# S7CAS-PLEIADES-CARTE-MERE_P07_FPGA_MISC.net
KiCad netlist of a schematic drawn in Altium Designer
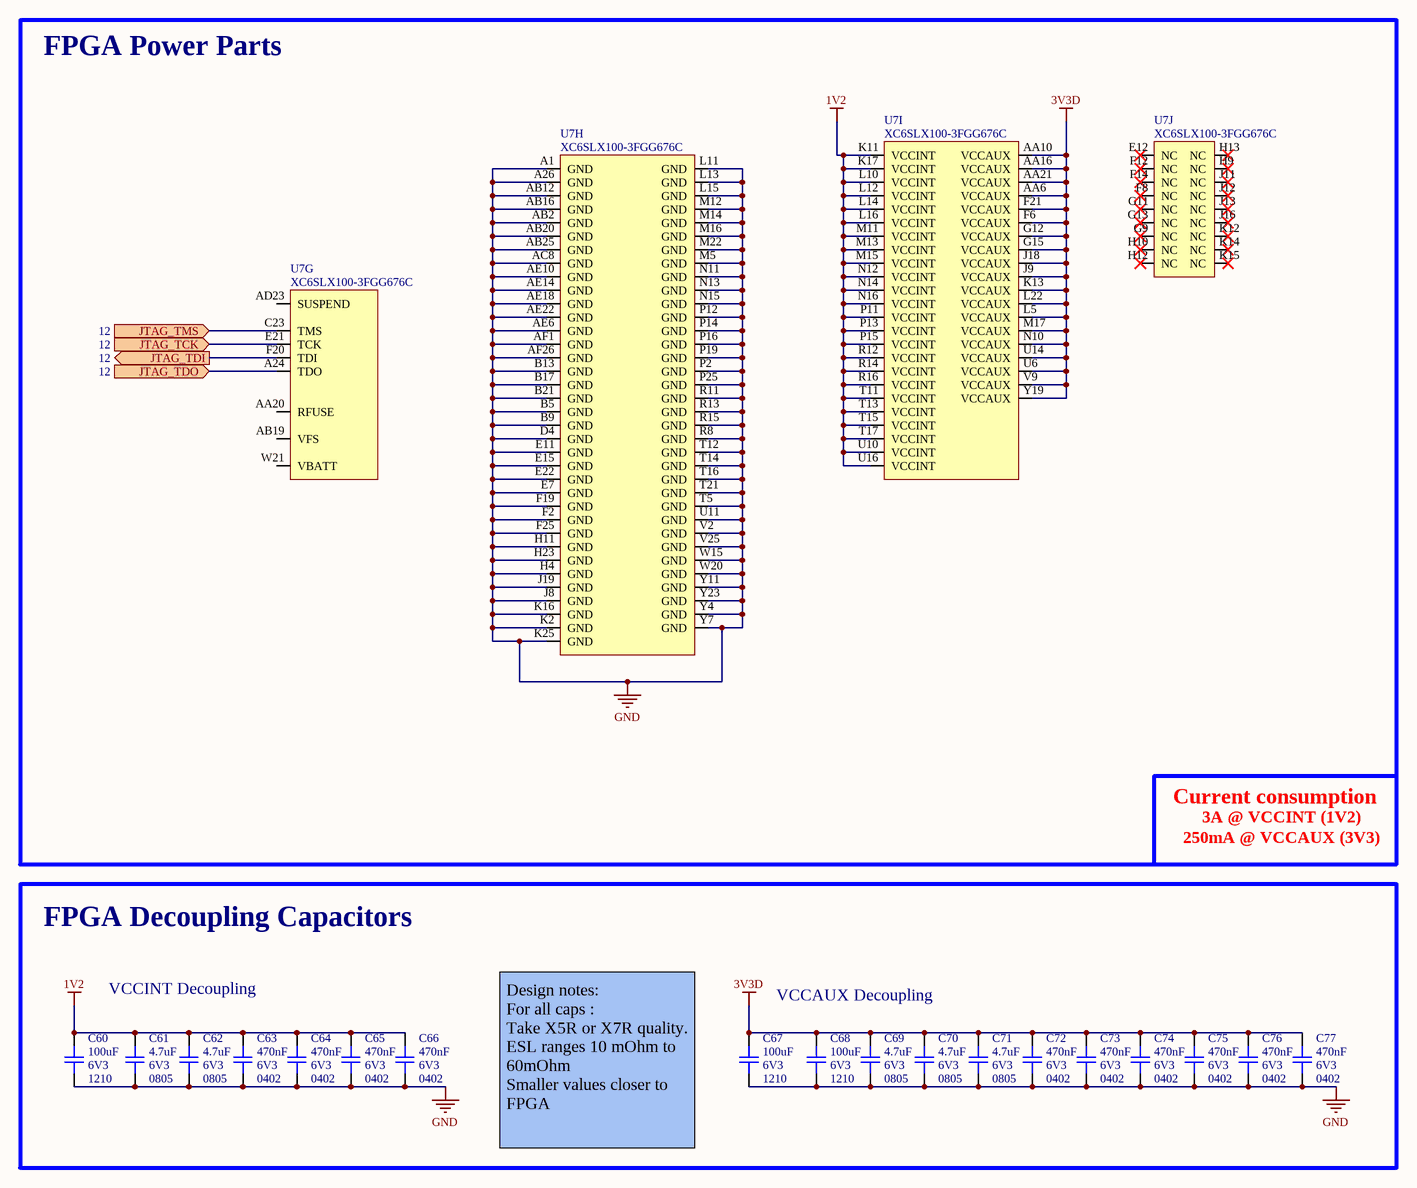
[diagram p0: S7CAS-PLEIADES-CARTE-MERE_P07_FPGA_MISC.SchDoc]

(export (version "E")
  (design (tool "Eeschema 10.0.6"))
  (components
    (comp (ref "C60")
      (value "100uF")
      (footprint "CAP_1210")
      (description "CAP - 1210")
      (fields
        (field (name "VOLTAGE") "6V3")
        (field (name "PACKAGE") "1210")
        (field (name "CREATEDBY") "Jonathan Bouchard")
      )
      (libsource (lib "S7CAS_LIB2021") (part "CAP - 1210"))
    )
    (comp (ref "C61")
      (value "4.7uF")
      (footprint "CAP_0805")
      (description "CAP - 0805")
      (fields
        (field (name "VOLTAGE") "6V3")
        (field (name "PACKAGE") "0805")
        (field (name "CREATEDBY") "Jonathan Bouchard")
      )
      (libsource (lib "S7CAS_LIB2021") (part "CAP - 0805"))
    )
    (comp (ref "C62")
      (value "4.7uF")
      (footprint "CAP_0805")
      (description "CAP - 0805")
      (fields
        (field (name "VOLTAGE") "6V3")
        (field (name "PACKAGE") "0805")
        (field (name "CREATEDBY") "Jonathan Bouchard")
      )
      (libsource (lib "S7CAS_LIB2021") (part "CAP - 0805"))
    )
    (comp (ref "C63")
      (value "470nF")
      (footprint "CAP_0402")
      (description "CAP - 0402")
      (fields
        (field (name "VOLTAGE") "6V3")
        (field (name "PACKAGE") "0402")
        (field (name "CREATEDBY") "Jonathan Bouchard")
      )
      (libsource (lib "S7CAS_LIB2021") (part "CAP - 0402"))
    )
    (comp (ref "C64")
      (value "470nF")
      (footprint "CAP_0402")
      (description "CAP - 0402")
      (fields
        (field (name "VOLTAGE") "6V3")
        (field (name "PACKAGE") "0402")
        (field (name "CREATEDBY") "Jonathan Bouchard")
      )
      (libsource (lib "S7CAS_LIB2021") (part "CAP - 0402"))
    )
    (comp (ref "C65")
      (value "470nF")
      (footprint "CAP_0402")
      (description "CAP - 0402")
      (fields
        (field (name "VOLTAGE") "6V3")
        (field (name "PACKAGE") "0402")
        (field (name "CREATEDBY") "Jonathan Bouchard")
      )
      (libsource (lib "S7CAS_LIB2021") (part "CAP - 0402"))
    )
    (comp (ref "C66")
      (value "470nF")
      (footprint "CAP_0402")
      (description "CAP - 0402")
      (fields
        (field (name "VOLTAGE") "6V3")
        (field (name "PACKAGE") "0402")
        (field (name "CREATEDBY") "Jonathan Bouchard")
      )
      (libsource (lib "S7CAS_LIB2021") (part "CAP - 0402"))
    )
    (comp (ref "C67")
      (value "100uF")
      (footprint "CAP_1210")
      (description "CAP - 1210")
      (fields
        (field (name "VOLTAGE") "6V3")
        (field (name "PACKAGE") "1210")
        (field (name "CREATEDBY") "Jonathan Bouchard")
      )
      (libsource (lib "S7CAS_LIB2021") (part "CAP - 1210"))
    )
    (comp (ref "C68")
      (value "100uF")
      (footprint "CAP_1210")
      (description "CAP - 1210")
      (fields
        (field (name "VOLTAGE") "6V3")
        (field (name "PACKAGE") "1210")
        (field (name "CREATEDBY") "Jonathan Bouchard")
      )
      (libsource (lib "S7CAS_LIB2021") (part "CAP - 1210"))
    )
    (comp (ref "C69")
      (value "4.7uF")
      (footprint "CAP_0805")
      (description "CAP - 0805")
      (fields
        (field (name "VOLTAGE") "6V3")
        (field (name "PACKAGE") "0805")
        (field (name "CREATEDBY") "Jonathan Bouchard")
      )
      (libsource (lib "S7CAS_LIB2021") (part "CAP - 0805"))
    )
    (comp (ref "C70")
      (value "4.7uF")
      (footprint "CAP_0805")
      (description "CAP - 0805")
      (fields
        (field (name "VOLTAGE") "6V3")
        (field (name "PACKAGE") "0805")
        (field (name "CREATEDBY") "Jonathan Bouchard")
      )
      (libsource (lib "S7CAS_LIB2021") (part "CAP - 0805"))
    )
    (comp (ref "C71")
      (value "4.7uF")
      (footprint "CAP_0805")
      (description "CAP - 0805")
      (fields
        (field (name "VOLTAGE") "6V3")
        (field (name "PACKAGE") "0805")
        (field (name "CREATEDBY") "Jonathan Bouchard")
      )
      (libsource (lib "S7CAS_LIB2021") (part "CAP - 0805"))
    )
    (comp (ref "C72")
      (value "470nF")
      (footprint "CAP_0402")
      (description "CAP - 0402")
      (fields
        (field (name "VOLTAGE") "6V3")
        (field (name "PACKAGE") "0402")
        (field (name "CREATEDBY") "Jonathan Bouchard")
      )
      (libsource (lib "S7CAS_LIB2021") (part "CAP - 0402"))
    )
    (comp (ref "C73")
      (value "470nF")
      (footprint "CAP_0402")
      (description "CAP - 0402")
      (fields
        (field (name "VOLTAGE") "6V3")
        (field (name "PACKAGE") "0402")
        (field (name "CREATEDBY") "Jonathan Bouchard")
      )
      (libsource (lib "S7CAS_LIB2021") (part "CAP - 0402"))
    )
    (comp (ref "C74")
      (value "470nF")
      (footprint "CAP_0402")
      (description "CAP - 0402")
      (fields
        (field (name "VOLTAGE") "6V3")
        (field (name "PACKAGE") "0402")
        (field (name "CREATEDBY") "Jonathan Bouchard")
      )
      (libsource (lib "S7CAS_LIB2021") (part "CAP - 0402"))
    )
    (comp (ref "C75")
      (value "470nF")
      (footprint "CAP_0402")
      (description "CAP - 0402")
      (fields
        (field (name "VOLTAGE") "6V3")
        (field (name "PACKAGE") "0402")
        (field (name "CREATEDBY") "Jonathan Bouchard")
      )
      (libsource (lib "S7CAS_LIB2021") (part "CAP - 0402"))
    )
    (comp (ref "C76")
      (value "470nF")
      (footprint "CAP_0402")
      (description "CAP - 0402")
      (fields
        (field (name "VOLTAGE") "6V3")
        (field (name "PACKAGE") "0402")
        (field (name "CREATEDBY") "Jonathan Bouchard")
      )
      (libsource (lib "S7CAS_LIB2021") (part "CAP - 0402"))
    )
    (comp (ref "C77")
      (value "470nF")
      (footprint "CAP_0402")
      (description "CAP - 0402")
      (fields
        (field (name "VOLTAGE") "6V3")
        (field (name "PACKAGE") "0402")
        (field (name "CREATEDBY") "Jonathan Bouchard")
      )
      (libsource (lib "S7CAS_LIB2021") (part "CAP - 0402"))
    )
    (comp (ref "U7")
      (value "XC6SLX100-3FGG676C")
      (footprint "FPGA_XILINX_FGG676")
      (description "FPGA - XILINX SPARTAN 6 480 I/O - BGA-676")
      (fields
        (field (name "VOLTAGE") "1.14 V ~ 1.26 V")
        (field (name "MFG") "Xilinx")
        (field (name "CREATEDBY") "Jonathan Bouchard")
      )
      (libsource (lib "S7CAS_LIB2021") (part "FPGA_XC6SLX100-3FGG676C"))
    )
  )
  (nets
    (net (code "1") (name "/JTAG_TCK") (class "Default")
      (node (ref "U7") (pin "E21") (pinfunction "TCK_E21") (pintype "passive"))
    )
    (net (code "2") (name "/JTAG_TDI") (class "Default")
      (node (ref "U7") (pin "F20") (pinfunction "TDI_F20") (pintype "passive"))
    )
    (net (code "3") (name "/JTAG_TDO") (class "Default")
      (node (ref "U7") (pin "A24") (pinfunction "TDO_A24") (pintype "passive"))
    )
    (net (code "4") (name "/JTAG_TMS") (class "Default")
      (node (ref "U7") (pin "C23") (pinfunction "TMS_C23") (pintype "passive"))
    )
    (net (code "5") (name "1V2") (class "Default")
      (node (ref "C60") (pin "2") (pinfunction "2_2") (pintype "passive"))
      (node (ref "C61") (pin "2") (pinfunction "2_2") (pintype "passive"))
      (node (ref "C62") (pin "2") (pinfunction "2_2") (pintype "passive"))
      (node (ref "C63") (pin "2") (pinfunction "2_2") (pintype "passive"))
      (node (ref "C64") (pin "2") (pinfunction "2_2") (pintype "passive"))
      (node (ref "C65") (pin "2") (pinfunction "2_2") (pintype "passive"))
      (node (ref "C66") (pin "2") (pinfunction "2_2") (pintype "passive"))
      (node (ref "U7") (pin "K11") (pinfunction "VCCINT_K11") (pintype "passive"))
      (node (ref "U7") (pin "K17") (pinfunction "VCCINT_K17") (pintype "passive"))
      (node (ref "U7") (pin "L10") (pinfunction "VCCINT_L10") (pintype "passive"))
      (node (ref "U7") (pin "L12") (pinfunction "VCCINT_L12") (pintype "passive"))
      (node (ref "U7") (pin "L14") (pinfunction "VCCINT_L14") (pintype "passive"))
      (node (ref "U7") (pin "L16") (pinfunction "VCCINT_L16") (pintype "passive"))
      (node (ref "U7") (pin "M11") (pinfunction "VCCINT_M11") (pintype "passive"))
      (node (ref "U7") (pin "M13") (pinfunction "VCCINT_M13") (pintype "passive"))
      (node (ref "U7") (pin "M15") (pinfunction "VCCINT_M15") (pintype "passive"))
      (node (ref "U7") (pin "N12") (pinfunction "VCCINT_N12") (pintype "passive"))
      (node (ref "U7") (pin "N14") (pinfunction "VCCINT_N14") (pintype "passive"))
      (node (ref "U7") (pin "N16") (pinfunction "VCCINT_N16") (pintype "passive"))
      (node (ref "U7") (pin "P11") (pinfunction "VCCINT_P11") (pintype "passive"))
      (node (ref "U7") (pin "P13") (pinfunction "VCCINT_P13") (pintype "passive"))
      (node (ref "U7") (pin "P15") (pinfunction "VCCINT_P15") (pintype "passive"))
      (node (ref "U7") (pin "R12") (pinfunction "VCCINT_R12") (pintype "passive"))
      (node (ref "U7") (pin "R14") (pinfunction "VCCINT_R14") (pintype "passive"))
      (node (ref "U7") (pin "R16") (pinfunction "VCCINT_R16") (pintype "passive"))
      (node (ref "U7") (pin "T11") (pinfunction "VCCINT_T11") (pintype "passive"))
      (node (ref "U7") (pin "T13") (pinfunction "VCCINT_T13") (pintype "passive"))
      (node (ref "U7") (pin "T15") (pinfunction "VCCINT_T15") (pintype "passive"))
      (node (ref "U7") (pin "T17") (pinfunction "VCCINT_T17") (pintype "passive"))
      (node (ref "U7") (pin "U10") (pinfunction "VCCINT_U10") (pintype "passive"))
      (node (ref "U7") (pin "U16") (pinfunction "VCCINT_U16") (pintype "passive"))
    )
    (net (code "6") (name "3V3D") (class "Default")
      (node (ref "C67") (pin "2") (pinfunction "2_2") (pintype "passive"))
      (node (ref "C68") (pin "2") (pinfunction "2_2") (pintype "passive"))
      (node (ref "C69") (pin "2") (pinfunction "2_2") (pintype "passive"))
      (node (ref "C70") (pin "2") (pinfunction "2_2") (pintype "passive"))
      (node (ref "C71") (pin "2") (pinfunction "2_2") (pintype "passive"))
      (node (ref "C72") (pin "2") (pinfunction "2_2") (pintype "passive"))
      (node (ref "C73") (pin "2") (pinfunction "2_2") (pintype "passive"))
      (node (ref "C74") (pin "2") (pinfunction "2_2") (pintype "passive"))
      (node (ref "C75") (pin "2") (pinfunction "2_2") (pintype "passive"))
      (node (ref "C76") (pin "2") (pinfunction "2_2") (pintype "passive"))
      (node (ref "C77") (pin "2") (pinfunction "2_2") (pintype "passive"))
      (node (ref "U7") (pin "AA10") (pinfunction "VCCAUX_AA10") (pintype "passive"))
      (node (ref "U7") (pin "AA16") (pinfunction "VCCAUX_AA16") (pintype "passive"))
      (node (ref "U7") (pin "AA21") (pinfunction "VCCAUX_AA21") (pintype "passive"))
      (node (ref "U7") (pin "AA6") (pinfunction "VCCAUX_AA6") (pintype "passive"))
      (node (ref "U7") (pin "F21") (pinfunction "VCCAUX_F21") (pintype "passive"))
      (node (ref "U7") (pin "F6") (pinfunction "VCCAUX_F6") (pintype "passive"))
      (node (ref "U7") (pin "G12") (pinfunction "VCCAUX_G12") (pintype "passive"))
      (node (ref "U7") (pin "G15") (pinfunction "VCCAUX_G15") (pintype "passive"))
      (node (ref "U7") (pin "J18") (pinfunction "VCCAUX_J18") (pintype "passive"))
      (node (ref "U7") (pin "J9") (pinfunction "VCCAUX_J9") (pintype "passive"))
      (node (ref "U7") (pin "K13") (pinfunction "VCCAUX_K13") (pintype "passive"))
      (node (ref "U7") (pin "L22") (pinfunction "VCCAUX_L22") (pintype "passive"))
      (node (ref "U7") (pin "L5") (pinfunction "VCCAUX_L5") (pintype "passive"))
      (node (ref "U7") (pin "M17") (pinfunction "VCCAUX_M17") (pintype "passive"))
      (node (ref "U7") (pin "N10") (pinfunction "VCCAUX_N10") (pintype "passive"))
      (node (ref "U7") (pin "U14") (pinfunction "VCCAUX_U14") (pintype "passive"))
      (node (ref "U7") (pin "U6") (pinfunction "VCCAUX_U6") (pintype "passive"))
      (node (ref "U7") (pin "V9") (pinfunction "VCCAUX_V9") (pintype "passive"))
      (node (ref "U7") (pin "Y19") (pinfunction "VCCAUX_Y19") (pintype "passive"))
    )
    (net (code "7") (name "GND") (class "Default")
      (node (ref "C60") (pin "1") (pinfunction "1_1") (pintype "passive"))
      (node (ref "C61") (pin "1") (pinfunction "1_1") (pintype "passive"))
      (node (ref "C62") (pin "1") (pinfunction "1_1") (pintype "passive"))
      (node (ref "C63") (pin "1") (pinfunction "1_1") (pintype "passive"))
      (node (ref "C64") (pin "1") (pinfunction "1_1") (pintype "passive"))
      (node (ref "C65") (pin "1") (pinfunction "1_1") (pintype "passive"))
      (node (ref "C66") (pin "1") (pinfunction "1_1") (pintype "passive"))
      (node (ref "C67") (pin "1") (pinfunction "1_1") (pintype "passive"))
      (node (ref "C68") (pin "1") (pinfunction "1_1") (pintype "passive"))
      (node (ref "C69") (pin "1") (pinfunction "1_1") (pintype "passive"))
      (node (ref "C70") (pin "1") (pinfunction "1_1") (pintype "passive"))
      (node (ref "C71") (pin "1") (pinfunction "1_1") (pintype "passive"))
      (node (ref "C72") (pin "1") (pinfunction "1_1") (pintype "passive"))
      (node (ref "C73") (pin "1") (pinfunction "1_1") (pintype "passive"))
      (node (ref "C74") (pin "1") (pinfunction "1_1") (pintype "passive"))
      (node (ref "C75") (pin "1") (pinfunction "1_1") (pintype "passive"))
      (node (ref "C76") (pin "1") (pinfunction "1_1") (pintype "passive"))
      (node (ref "C77") (pin "1") (pinfunction "1_1") (pintype "passive"))
      (node (ref "U7") (pin "A1") (pinfunction "GND_A1") (pintype "passive"))
      (node (ref "U7") (pin "A26") (pinfunction "GND_A26") (pintype "passive"))
      (node (ref "U7") (pin "AB12") (pinfunction "GND_AB12") (pintype "passive"))
      (node (ref "U7") (pin "AB16") (pinfunction "GND_AB16") (pintype "passive"))
      (node (ref "U7") (pin "AB2") (pinfunction "GND_AB2") (pintype "passive"))
      (node (ref "U7") (pin "AB20") (pinfunction "GND_AB20") (pintype "passive"))
      (node (ref "U7") (pin "AB25") (pinfunction "GND_AB25") (pintype "passive"))
      (node (ref "U7") (pin "AC8") (pinfunction "GND_AC8") (pintype "passive"))
      (node (ref "U7") (pin "AE10") (pinfunction "GND_AE10") (pintype "passive"))
      (node (ref "U7") (pin "AE14") (pinfunction "GND_AE14") (pintype "passive"))
      (node (ref "U7") (pin "AE18") (pinfunction "GND_AE18") (pintype "passive"))
      (node (ref "U7") (pin "AE22") (pinfunction "GND_AE22") (pintype "passive"))
      (node (ref "U7") (pin "AE6") (pinfunction "GND_AE6") (pintype "passive"))
      (node (ref "U7") (pin "AF1") (pinfunction "GND_AF1") (pintype "passive"))
      (node (ref "U7") (pin "AF26") (pinfunction "GND_AF26") (pintype "passive"))
      (node (ref "U7") (pin "B13") (pinfunction "GND_B13") (pintype "passive"))
      (node (ref "U7") (pin "B17") (pinfunction "GND_B17") (pintype "passive"))
      (node (ref "U7") (pin "B21") (pinfunction "GND_B21") (pintype "passive"))
      (node (ref "U7") (pin "B5") (pinfunction "GND_B5") (pintype "passive"))
      (node (ref "U7") (pin "B9") (pinfunction "GND_B9") (pintype "passive"))
      (node (ref "U7") (pin "D4") (pinfunction "GND_D4") (pintype "passive"))
      (node (ref "U7") (pin "E11") (pinfunction "GND_E11") (pintype "passive"))
      (node (ref "U7") (pin "E15") (pinfunction "GND_E15") (pintype "passive"))
      (node (ref "U7") (pin "E22") (pinfunction "GND_E22") (pintype "passive"))
      (node (ref "U7") (pin "E7") (pinfunction "GND_E7") (pintype "passive"))
      (node (ref "U7") (pin "F19") (pinfunction "GND_F19") (pintype "passive"))
      (node (ref "U7") (pin "F2") (pinfunction "GND_F2") (pintype "passive"))
      (node (ref "U7") (pin "F25") (pinfunction "GND_F25") (pintype "passive"))
      (node (ref "U7") (pin "H11") (pinfunction "GND_H11") (pintype "passive"))
      (node (ref "U7") (pin "H23") (pinfunction "GND_H23") (pintype "passive"))
      (node (ref "U7") (pin "H4") (pinfunction "GND_H4") (pintype "passive"))
      (node (ref "U7") (pin "J19") (pinfunction "GND_J19") (pintype "passive"))
      (node (ref "U7") (pin "J8") (pinfunction "GND_J8") (pintype "passive"))
      (node (ref "U7") (pin "K16") (pinfunction "GND_K16") (pintype "passive"))
      (node (ref "U7") (pin "K2") (pinfunction "GND_K2") (pintype "passive"))
      (node (ref "U7") (pin "K25") (pinfunction "GND_K25") (pintype "passive"))
      (node (ref "U7") (pin "L11") (pinfunction "GND_L11") (pintype "passive"))
      (node (ref "U7") (pin "L13") (pinfunction "GND_L13") (pintype "passive"))
      (node (ref "U7") (pin "L15") (pinfunction "GND_L15") (pintype "passive"))
      (node (ref "U7") (pin "M12") (pinfunction "GND_M12") (pintype "passive"))
      (node (ref "U7") (pin "M14") (pinfunction "GND_M14") (pintype "passive"))
      (node (ref "U7") (pin "M16") (pinfunction "GND_M16") (pintype "passive"))
      (node (ref "U7") (pin "M22") (pinfunction "GND_M22") (pintype "passive"))
      (node (ref "U7") (pin "M5") (pinfunction "GND_M5") (pintype "passive"))
      (node (ref "U7") (pin "N11") (pinfunction "GND_N11") (pintype "passive"))
      (node (ref "U7") (pin "N13") (pinfunction "GND_N13") (pintype "passive"))
      (node (ref "U7") (pin "N15") (pinfunction "GND_N15") (pintype "passive"))
      (node (ref "U7") (pin "P12") (pinfunction "GND_P12") (pintype "passive"))
      (node (ref "U7") (pin "P14") (pinfunction "GND_P14") (pintype "passive"))
      (node (ref "U7") (pin "P16") (pinfunction "GND_P16") (pintype "passive"))
      (node (ref "U7") (pin "P19") (pinfunction "GND_P19") (pintype "passive"))
      (node (ref "U7") (pin "P2") (pinfunction "GND_P2") (pintype "passive"))
      (node (ref "U7") (pin "P25") (pinfunction "GND_P25") (pintype "passive"))
      (node (ref "U7") (pin "R11") (pinfunction "GND_R11") (pintype "passive"))
      (node (ref "U7") (pin "R13") (pinfunction "GND_R13") (pintype "passive"))
      (node (ref "U7") (pin "R15") (pinfunction "GND_R15") (pintype "passive"))
      (node (ref "U7") (pin "R8") (pinfunction "GND_R8") (pintype "passive"))
      (node (ref "U7") (pin "T12") (pinfunction "GND_T12") (pintype "passive"))
      (node (ref "U7") (pin "T14") (pinfunction "GND_T14") (pintype "passive"))
      (node (ref "U7") (pin "T16") (pinfunction "GND_T16") (pintype "passive"))
      (node (ref "U7") (pin "T21") (pinfunction "GND_T21") (pintype "passive"))
      (node (ref "U7") (pin "T5") (pinfunction "GND_T5") (pintype "passive"))
      (node (ref "U7") (pin "U11") (pinfunction "GND_U11") (pintype "passive"))
      (node (ref "U7") (pin "V2") (pinfunction "GND_V2") (pintype "passive"))
      (node (ref "U7") (pin "V25") (pinfunction "GND_V25") (pintype "passive"))
      (node (ref "U7") (pin "W15") (pinfunction "GND_W15") (pintype "passive"))
      (node (ref "U7") (pin "W20") (pinfunction "GND_W20") (pintype "passive"))
      (node (ref "U7") (pin "Y11") (pinfunction "GND_Y11") (pintype "passive"))
      (node (ref "U7") (pin "Y23") (pinfunction "GND_Y23") (pintype "passive"))
      (node (ref "U7") (pin "Y4") (pinfunction "GND_Y4") (pintype "passive"))
      (node (ref "U7") (pin "Y7") (pinfunction "GND_Y7") (pintype "passive"))
    )
    (net (code "8") (name "unconnected-(U7G-RFUSE-PadAA20)") (class "Default")
      (node (ref "U7") (pin "AA20") (pinfunction "RFUSE_AA20") (pintype "passive"))
    )
    (net (code "9") (name "unconnected-(U7G-SUSPEND-PadAD23)") (class "Default")
      (node (ref "U7") (pin "AD23") (pinfunction "SUSPEND_AD23") (pintype "passive"))
    )
    (net (code "10") (name "unconnected-(U7G-VBATT-PadW21)") (class "Default")
      (node (ref "U7") (pin "W21") (pinfunction "VBATT_W21") (pintype "passive"))
    )
    (net (code "11") (name "unconnected-(U7G-VFS-PadAB19)") (class "Default")
      (node (ref "U7") (pin "AB19") (pinfunction "VFS_AB19") (pintype "passive"))
    )
    (net (code "12") (name "unconnected-(U7J-NC-PadE12)") (class "Default")
      (node (ref "U7") (pin "E12") (pinfunction "NC_E12") (pintype "passive+no_connect"))
    )
    (net (code "13") (name "unconnected-(U7J-NC-PadF8)") (class "Default")
      (node (ref "U7") (pin "F8") (pinfunction "NC_F8") (pintype "passive+no_connect"))
    )
    (net (code "14") (name "unconnected-(U7J-NC-PadF12)") (class "Default")
      (node (ref "U7") (pin "F12") (pinfunction "NC_F12") (pintype "passive+no_connect"))
    )
    (net (code "15") (name "unconnected-(U7J-NC-PadF14)") (class "Default")
      (node (ref "U7") (pin "F14") (pinfunction "NC_F14") (pintype "passive+no_connect"))
    )
    (net (code "16") (name "unconnected-(U7J-NC-PadG9)") (class "Default")
      (node (ref "U7") (pin "G9") (pinfunction "NC_G9") (pintype "passive+no_connect"))
    )
    (net (code "17") (name "unconnected-(U7J-NC-PadG11)") (class "Default")
      (node (ref "U7") (pin "G11") (pinfunction "NC_G11") (pintype "passive+no_connect"))
    )
    (net (code "18") (name "unconnected-(U7J-NC-PadG13)") (class "Default")
      (node (ref "U7") (pin "G13") (pinfunction "NC_G13") (pintype "passive+no_connect"))
    )
    (net (code "19") (name "unconnected-(U7J-NC-PadH9)") (class "Default")
      (node (ref "U7") (pin "H9") (pinfunction "NC_H9") (pintype "passive+no_connect"))
    )
    (net (code "20") (name "unconnected-(U7J-NC-PadH10)") (class "Default")
      (node (ref "U7") (pin "H10") (pinfunction "NC_H10") (pintype "passive+no_connect"))
    )
    (net (code "21") (name "unconnected-(U7J-NC-PadH12)") (class "Default")
      (node (ref "U7") (pin "H12") (pinfunction "NC_H12") (pintype "passive+no_connect"))
    )
    (net (code "22") (name "unconnected-(U7J-NC-PadH13)") (class "Default")
      (node (ref "U7") (pin "H13") (pinfunction "NC_H13") (pintype "passive+no_connect"))
    )
    (net (code "23") (name "unconnected-(U7J-NC-PadJ11)") (class "Default")
      (node (ref "U7") (pin "J11") (pinfunction "NC_J11") (pintype "passive+no_connect"))
    )
    (net (code "24") (name "unconnected-(U7J-NC-PadJ12)") (class "Default")
      (node (ref "U7") (pin "J12") (pinfunction "NC_J12") (pintype "passive+no_connect"))
    )
    (net (code "25") (name "unconnected-(U7J-NC-PadJ13)") (class "Default")
      (node (ref "U7") (pin "J13") (pinfunction "NC_J13") (pintype "passive+no_connect"))
    )
    (net (code "26") (name "unconnected-(U7J-NC-PadJ16)") (class "Default")
      (node (ref "U7") (pin "J16") (pinfunction "NC_J16") (pintype "passive+no_connect"))
    )
    (net (code "27") (name "unconnected-(U7J-NC-PadK12)") (class "Default")
      (node (ref "U7") (pin "K12") (pinfunction "NC_K12") (pintype "passive+no_connect"))
    )
    (net (code "28") (name "unconnected-(U7J-NC-PadK14)") (class "Default")
      (node (ref "U7") (pin "K14") (pinfunction "NC_K14") (pintype "passive+no_connect"))
    )
    (net (code "29") (name "unconnected-(U7J-NC-PadK15)") (class "Default")
      (node (ref "U7") (pin "K15") (pinfunction "NC_K15") (pintype "passive+no_connect"))
    )
  )
)
